# LED.net
KiCad netlist of a schematic drawn in Altium Designer
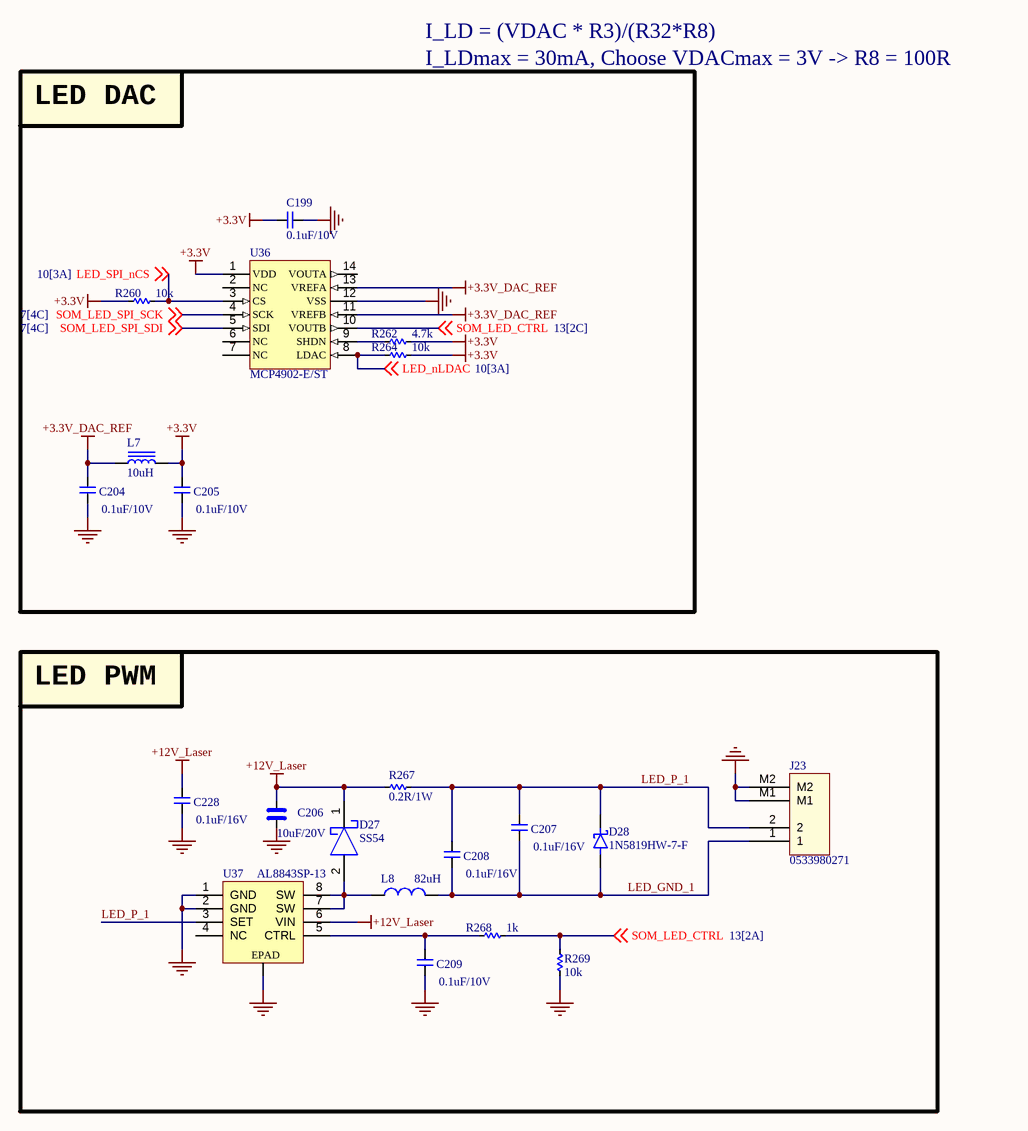
[diagram p0: LED.SchDoc]

(export (version "E")
  (design (tool "Eeschema 10.0.6"))
  (components
    (comp (ref "C199")
      (value "0.1uF/10V")
      (footprint "CAP_C_1005X60")
      (description "CAP CHIP")
      (libsource (lib "LABLIB") (part "_CAP_C_2"))
    )
    (comp (ref "C204")
      (value "0.1uF/10V")
      (footprint "CAP_C_1005X60")
      (description "CAP CHIP")
      (libsource (lib "LABLIB") (part "_CAP_C_2"))
    )
    (comp (ref "C205")
      (value "0.1uF/10V")
      (footprint "CAP_C_1005X60")
      (description "CAP CHIP")
      (libsource (lib "LABLIB") (part "_CAP_C_2"))
    )
    (comp (ref "C206")
      (value "10uF/20V")
      (footprint "CAP_C_2012X110")
      (description "CAP CHIP High Value")
      (libsource (lib "LABLIB") (part "_CAP_C_High_2"))
    )
    (comp (ref "C207")
      (value "0.1uF/16V")
      (footprint "CAP_C_1005X60")
      (description "CAP CHIP")
      (libsource (lib "LABLIB") (part "_CAP_C_2"))
    )
    (comp (ref "C208")
      (value "0.1uF/16V")
      (footprint "CAP_C_1005X60")
      (description "CAP CHIP")
      (libsource (lib "LABLIB") (part "_CAP_C_2"))
    )
    (comp (ref "C209")
      (value "0.1uF/10V")
      (footprint "CAP_C_1005X60")
      (description "CAP CHIP")
      (libsource (lib "LABLIB") (part "_CAP_C_2"))
    )
    (comp (ref "C228")
      (value "0.1uF/16V")
      (footprint "CAP_C_1005X60")
      (description "CAP CHIP")
      (libsource (lib "LABLIB") (part "_CAP_C_2"))
    )
    (comp (ref "D27")
      (value "SS54")
      (footprint "DO-214AC_SMA")
      (description "DIODE SCHOTTKY 60V 3A DO214AA")
      (libsource (lib "EXP_HW_V3") (part "SS54"))
    )
    (comp (ref "D28")
      (value "1N5819HW-7-F")
      (footprint "SOD3717X145N")
      (description "DIODE SCHOTTKY 40V 1A SOD123")
      (libsource (lib "LABLIB") (part "DIODE SCHOTTKY"))
    )
    (comp (ref "J23")
      (value "0533980271")
      (footprint "MOLEX_0533980271")
      (libsource (lib "LABLIB") (part "Header 2x1_2M"))
    )
    (comp (ref "L7")
      (value "10uH")
      (footprint "IND_C_2012X65")
      (description "MLZ1608N100LT000")
      (libsource (lib "INDUCTOR") (part "Inductor"))
    )
    (comp (ref "L8")
      (value "82uH")
      (footprint "L-SMD-M-4.8x4.8x2.8mm")
      (description "SRR4828A-820M")
      (fields
        (field (name "PARTNO") "78477010")
        (field (name "MANUFACTURER") "Wurth Elektronik")
        (field (name "CREATED BY") "Baojun Chen")
      )
      (libsource (lib "EXP_HW_V3") (part "L-SMD-1"))
    )
    (comp (ref "R260")
      (value "10k")
      (footprint "RES_C_1005X40")
      (description "RES")
      (libsource (lib "LABLIB") (part "_RES_B_2"))
    )
    (comp (ref "R262")
      (value "4.7k")
      (footprint "RES_C_1005X40")
      (description "RES")
      (libsource (lib "LABLIB") (part "_RES_B_2"))
    )
    (comp (ref "R264")
      (value "10k")
      (footprint "RES_C_1005X40")
      (description "RES")
      (libsource (lib "LABLIB") (part "_RES_B_2"))
    )
    (comp (ref "R267")
      (value "0.2R/1W")
      (footprint "RES_C_3216X70")
      (description "RES")
      (libsource (lib "LABLIB") (part "_RES_B_2"))
    )
    (comp (ref "R268")
      (value "1k")
      (footprint "RES_C_1005X40")
      (description "RES")
      (libsource (lib "LABLIB") (part "_RES_B_2"))
    )
    (comp (ref "R269")
      (value "10k")
      (footprint "RES_C_1005X40")
      (description "RES")
      (libsource (lib "LABLIB") (part "_RES_B_2"))
    )
    (comp (ref "U36")
      (value "MCP4902-E/ST")
      (footprint "SOIC127P600X175-14N")
      (description "IC DAC 8BIT V-OUT 14TSSOP")
      (libsource (lib "Library") (part "MCP4902"))
    )
    (comp (ref "U37")
      (value "AL8843SP-13")
      (footprint "SOIC127P602X173-8N_EPAD")
      (description "IC LED DRIVER RGLTR PWM 3A 8SO")
      (libsource (lib "EXP_HW_V3") (part "AL8843SP-13"))
    )
  )
  (nets
    (net (code "1") (name "+3.3V") (class "Default")
      (node (ref "C199") (pin "2") (pinfunction "2_2") (pintype "passive"))
      (node (ref "C205") (pin "2") (pinfunction "2_2") (pintype "passive"))
      (node (ref "L7") (pin "2") (pinfunction "2_2") (pintype "passive"))
      (node (ref "R260") (pin "1") (pinfunction "1_1") (pintype "passive"))
      (node (ref "R262") (pin "2") (pinfunction "2_2") (pintype "passive"))
      (node (ref "R264") (pin "2") (pinfunction "2_2") (pintype "passive"))
      (node (ref "U36") (pin "1") (pinfunction "VDD_1") (pintype "power_in"))
    )
    (net (code "2") (name "+3.3V_DAC_REF") (class "Default")
      (node (ref "C204") (pin "2") (pinfunction "2_2") (pintype "passive"))
      (node (ref "L7") (pin "1") (pinfunction "1_1") (pintype "passive"))
      (node (ref "U36") (pin "11") (pinfunction "VREFB_11") (pintype "input"))
      (node (ref "U36") (pin "13") (pinfunction "VREFA_13") (pintype "input"))
    )
    (net (code "3") (name "+12V_Laser") (class "Default")
      (node (ref "C206") (pin "1") (pinfunction "1_1") (pintype "passive"))
      (node (ref "C228") (pin "2") (pinfunction "2_2") (pintype "passive"))
      (node (ref "D27") (pin "1") (pinfunction "1_1") (pintype "passive"))
      (node (ref "R267") (pin "2") (pinfunction "2_2") (pintype "passive"))
      (node (ref "U37") (pin "6") (pinfunction "VIN_6") (pintype "passive"))
    )
    (net (code "4") (name "/LED_GND_1") (class "Default")
      (node (ref "C207") (pin "1") (pinfunction "1_1") (pintype "passive"))
      (node (ref "C208") (pin "1") (pinfunction "1_1") (pintype "passive"))
      (node (ref "D28") (pin "2") (pinfunction "A_2") (pintype "passive"))
      (node (ref "J23") (pin "1") (pinfunction "1_1") (pintype "passive"))
      (node (ref "L8") (pin "2") (pinfunction "2_2") (pintype "passive"))
    )
    (net (code "5") (name "/LED_P_1") (class "Default")
      (node (ref "C207") (pin "2") (pinfunction "2_2") (pintype "passive"))
      (node (ref "C208") (pin "2") (pinfunction "2_2") (pintype "passive"))
      (node (ref "D28") (pin "1") (pinfunction "K_1") (pintype "passive"))
      (node (ref "J23") (pin "2") (pinfunction "2_2") (pintype "passive"))
      (node (ref "R267") (pin "1") (pinfunction "1_1") (pintype "passive"))
      (node (ref "U37") (pin "3") (pinfunction "SET_3") (pintype "passive"))
    )
    (net (code "6") (name "GND") (class "Default")
      (node (ref "C199") (pin "1") (pinfunction "1_1") (pintype "passive"))
      (node (ref "C204") (pin "1") (pinfunction "1_1") (pintype "passive"))
      (node (ref "C205") (pin "1") (pinfunction "1_1") (pintype "passive"))
      (node (ref "C206") (pin "2") (pinfunction "2_2") (pintype "passive"))
      (node (ref "C209") (pin "1") (pinfunction "1_1") (pintype "passive"))
      (node (ref "C228") (pin "1") (pinfunction "1_1") (pintype "passive"))
      (node (ref "J23") (pin "M1") (pinfunction "M1_M1") (pintype "passive"))
      (node (ref "J23") (pin "M2") (pinfunction "M2_M2") (pintype "passive"))
      (node (ref "R269") (pin "1") (pinfunction "1_1") (pintype "passive"))
      (node (ref "U36") (pin "12") (pinfunction "VSS_12") (pintype "power_in"))
      (node (ref "U37") (pin "1") (pinfunction "GND_1") (pintype "passive"))
      (node (ref "U37") (pin "2") (pinfunction "GND_2") (pintype "passive"))
      (node (ref "U37") (pin "EPAD") (pinfunction "EPAD_EPAD") (pintype "passive"))
    )
    (net (code "7") (name "LED_SPI_nCS") (class "Default")
      (node (ref "R260") (pin "2") (pinfunction "2_2") (pintype "passive"))
      (node (ref "U36") (pin "3") (pinfunction "CS_3") (pintype "input"))
    )
    (net (code "8") (name "LED_nLDAC") (class "Default")
      (node (ref "R264") (pin "1") (pinfunction "1_1") (pintype "passive"))
      (node (ref "U36") (pin "8") (pinfunction "LDAC_8") (pintype "input"))
    )
    (net (code "9") (name "Net-(D27-Pad2)") (class "Default")
      (node (ref "D27") (pin "2") (pinfunction "2_2") (pintype "passive"))
      (node (ref "L8") (pin "1") (pinfunction "1_1") (pintype "passive"))
      (node (ref "U37") (pin "7") (pinfunction "SW_7") (pintype "passive"))
      (node (ref "U37") (pin "8") (pinfunction "SW_8") (pintype "passive"))
    )
    (net (code "10") (name "Net-(U36-SHDN)") (class "Default")
      (node (ref "R262") (pin "1") (pinfunction "1_1") (pintype "passive"))
      (node (ref "U36") (pin "9") (pinfunction "SHDN_9") (pintype "input"))
    )
    (net (code "11") (name "Net-(U37-CTRL)") (class "Default")
      (node (ref "C209") (pin "2") (pinfunction "2_2") (pintype "passive"))
      (node (ref "R268") (pin "1") (pinfunction "1_1") (pintype "passive"))
      (node (ref "U37") (pin "5") (pinfunction "CTRL_5") (pintype "passive"))
    )
    (net (code "12") (name "SOM_LED_CTRL") (class "Default")
      (node (ref "R268") (pin "2") (pinfunction "2_2") (pintype "passive"))
      (node (ref "R269") (pin "2") (pinfunction "2_2") (pintype "passive"))
      (node (ref "U36") (pin "10") (pinfunction "VOUTB_10") (pintype "output"))
    )
    (net (code "13") (name "SOM_LED_SPI_SCK") (class "Default")
      (node (ref "U36") (pin "4") (pinfunction "SCK_4") (pintype "input"))
    )
    (net (code "14") (name "SOM_LED_SPI_SDI") (class "Default")
      (node (ref "U36") (pin "5") (pinfunction "SDI_5") (pintype "input"))
    )
    (net (code "15") (name "unconnected-(U36-NC-Pad2)") (class "Default")
      (node (ref "U36") (pin "2") (pinfunction "NC_2") (pintype "tri_state"))
    )
    (net (code "16") (name "unconnected-(U36-NC-Pad6)") (class "Default")
      (node (ref "U36") (pin "6") (pinfunction "NC_6") (pintype "tri_state"))
    )
    (net (code "17") (name "unconnected-(U36-NC-Pad7)") (class "Default")
      (node (ref "U36") (pin "7") (pinfunction "NC_7") (pintype "tri_state"))
    )
    (net (code "18") (name "unconnected-(U36-VOUTA-Pad14)") (class "Default")
      (node (ref "U36") (pin "14") (pinfunction "VOUTA_14") (pintype "output"))
    )
    (net (code "19") (name "unconnected-(U37-NC-Pad4)") (class "Default")
      (node (ref "U37") (pin "4") (pinfunction "NC_4") (pintype "passive"))
    )
  )
)
